# HA_HiPower.net
KiCad netlist of a schematic drawn in Altium Designer
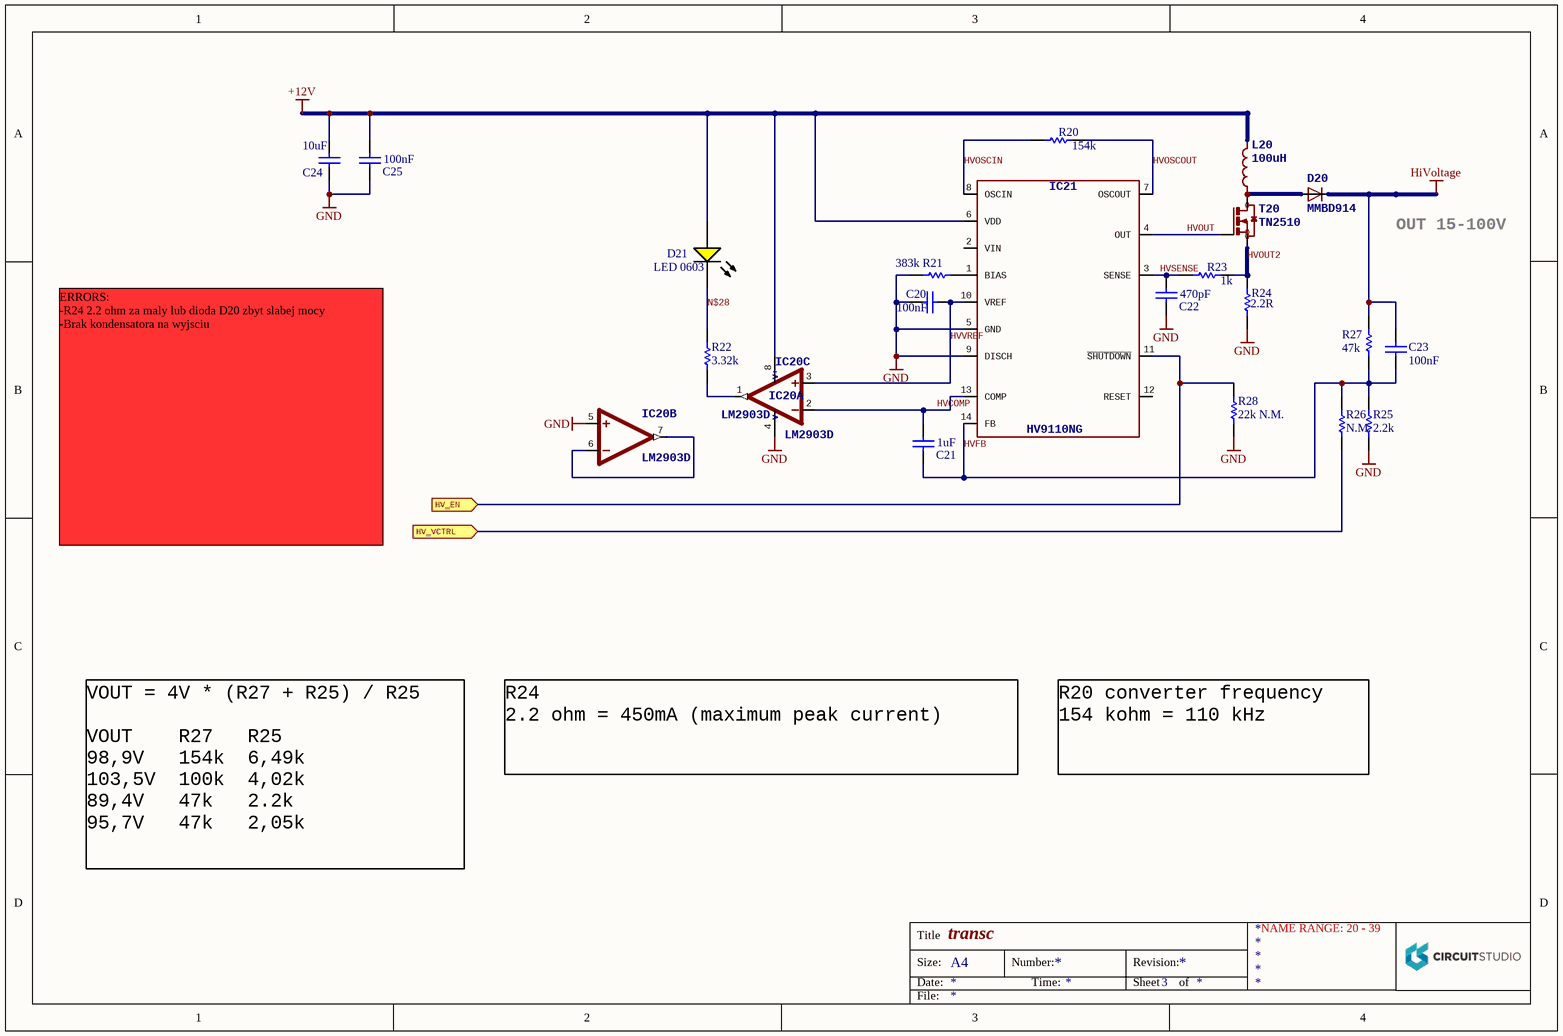
[diagram p0: HA_HiPower.SchDoc]

(export (version "E")
  (design (tool "Eeschema 10.0.6"))
  (components
    (comp (ref "C20")
      (value "100nF")
      (footprint "CAPC0805(2012)145_L")
      (fields (field (name "TOLERANCE") "Â±20%") (field (name "Comment") "100nF 100V"))
      (libsource (lib "Altium Content Vault") (part "CMP-1036-04431-1"))
    )
    (comp (ref "C21")
      (value "1uF")
      (footprint "CAPC0805(2012)145_L")
      (fields (field (name "TOLERANCE") "Â±20%") (field (name "Comment") "1uF 100V"))
      (libsource (lib "Altium Content Vault") (part "CMP-1036-04431-1"))
    )
    (comp (ref "C22")
      (value "470pF")
      (footprint "CAPC0805(2012)145_L")
      (fields (field (name "TOLERANCE") "Â±20%") (field (name "Comment") "470pF 100V"))
      (libsource (lib "Altium Content Vault") (part "CMP-1036-04431-1"))
    )
    (comp (ref "C23")
      (value "100nF")
      (footprint "CAPC0805(2012)145_L")
      (fields (field (name "TOLERANCE") "Â±20%") (field (name "Comment") "100nF 100V"))
      (libsource (lib "Altium Content Vault") (part "CMP-1036-04431-1"))
    )
    (comp (ref "C24")
      (value "10uF")
      (footprint "CAPC1206(3216)190_N")
      (description "CAP 1206 (3216 Metric) Thickness 1.9mm SMD")
      (fields (field (name "TOLERANCE") "Â±20%") (field (name "Comment") "10uF 35V"))
      (libsource (lib "Altium Content Vault") (part "CMP-1037-04990-1"))
    )
    (comp (ref "C25")
      (value "100nF")
      (footprint "CAPC0805(2012)145_L")
      (fields (field (name "TOLERANCE") "Â±20%") (field (name "Comment") "100nF 100V"))
      (libsource (lib "Altium Content Vault") (part "CMP-1036-04431-1"))
    )
    (comp (ref "D20")
      (value "MMBD914")
      (footprint "SOT23")
      (libsource (lib "_toan_elem") (part "DIODE-SOT23"))
    )
    (comp (ref "D21")
      (value "LED 0603")
      (footprint "LTST-C190KSKT_V")
      (fields (field (name "TOLERANCE") "1%"))
      (libsource (lib "Altium Content Vault") (part "CMP-1674-00009-1"))
    )
    (comp (ref "IC20")
      (value "LM2903D")
      (footprint "SO08")
      (description "COMPARATOR")
      (fields (field (name "V+") "V+") (field (name "V-") "V-"))
      (libsource (lib "uw") (part "LM2903D"))
    )
    (comp (ref "IC21")
      (value "HV9110NG")
      (footprint "SOIC14")
      (libsource (lib "microchip") (part "HV9110NG"))
    )
    (comp (ref "L20")
      (value "100uH")
      (footprint "LPS8045B")
      (fields (field (name "MPN") "LPS8045B-104"))
      (libsource (lib "_toan_elem") (part "LDE1205"))
    )
    (comp (ref "R20")
      (value "154k")
      (footprint "RESC0603(1608)_N")
      (description "1% 0603 SMD")
      (fields (field (name "TOLERANCE") "1 %"))
      (libsource (lib "Altium Content Vault") (part "CMP-1012-00122-1"))
    )
    (comp (ref "R21")
      (value "383k")
      (footprint "RESC0603(1608)_N")
      (description "1% 0603 SMD")
      (fields (field (name "TOLERANCE") "1 %"))
      (libsource (lib "Altium Content Vault") (part "CMP-1012-00122-1"))
    )
    (comp (ref "R22")
      (value "3.32k")
      (footprint "RESC0603(1608)_N")
      (description "1% 0603 SMD")
      (fields (field (name "TOLERANCE") "1 %"))
      (libsource (lib "Altium Content Vault") (part "CMP-1012-00122-1"))
    )
    (comp (ref "R23")
      (value "1k")
      (footprint "RESC0603(1608)_N")
      (description "1% 0603 SMD")
      (fields (field (name "TOLERANCE") "1 %"))
      (libsource (lib "Altium Content Vault") (part "CMP-1012-00122-1"))
    )
    (comp (ref "R24")
      (value "2.2R")
      (footprint "RESC2512(6432)_M")
      (description "2.2R 1W 5% 2512 SMD")
      (fields (field (name "TOLERANCE") "5 %") (field (name "POWER") "1 W"))
      (libsource (lib "Altium Content Vault") (part "CMP-1018-00050-1"))
    )
    (comp (ref "R25")
      (value "2.2k")
      (footprint "RESC0603(1608)_N")
      (description "1% 0603 SMD")
      (fields (field (name "TOLERANCE") "1 %"))
      (libsource (lib "Altium Content Vault") (part "CMP-1012-00122-1"))
    )
    (comp (ref "R26")
      (value "N.M.")
      (footprint "RESC0603(1608)_N")
      (description "1% 0603 SMD")
      (fields (field (name "TOLERANCE") "1 %"))
      (libsource (lib "Altium Content Vault") (part "CMP-1012-00122-1"))
    )
    (comp (ref "R27")
      (value "47k")
      (footprint "RESC0603(1608)_N")
      (description "1% 0603 SMD")
      (fields (field (name "TOLERANCE") "1 %"))
      (libsource (lib "Altium Content Vault") (part "CMP-1012-00122-1"))
    )
    (comp (ref "R28")
      (value "22k N.M.")
      (footprint "RESC0603(1608)_N")
      (description "1% 0603 SMD")
      (fields (field (name "TOLERANCE") "1 %"))
      (libsource (lib "Altium Content Vault") (part "CMP-1012-00122-1"))
    )
    (comp (ref "T20") (value "TN2510") (footprint "SOT89") (libsource (lib "uw") (part "MOSFET_NSOT89")))
  )
  (nets
    (net (code "1") (name "+12V") (class "Default")
      (node (ref "C24") (pin "2") (pinfunction "2_2") (pintype "passive"))
      (node (ref "C25") (pin "2") (pinfunction "2_2") (pintype "passive"))
      (node (ref "D21") (pin "1") (pinfunction "A_1") (pintype "passive"))
      (node (ref "IC20") (pin "8") (pinfunction "V+_8") (pintype "power_in"))
      (node (ref "IC21") (pin "6") (pinfunction "VDD_6") (pintype "power_in"))
      (node (ref "L20") (pin "2") (pinfunction "2_2") (pintype "passive"))
    )
    (net (code "2") (name "/HVCOMP") (class "Default")
      (node (ref "C21") (pin "2") (pinfunction "2_2") (pintype "passive"))
      (node (ref "IC20") (pin "2") (pinfunction "-IN_2") (pintype "passive"))
      (node (ref "IC21") (pin "13") (pinfunction "COMP_13") (pintype "passive"))
    )
    (net (code "3") (name "/HVFB") (class "Default")
      (node (ref "C21") (pin "1") (pinfunction "1_1") (pintype "passive"))
      (node (ref "C23") (pin "2") (pinfunction "2_2") (pintype "passive"))
      (node (ref "IC21") (pin "14") (pinfunction "FB_14") (pintype "passive"))
      (node (ref "R25") (pin "2") (pinfunction "2_2") (pintype "passive"))
      (node (ref "R26") (pin "2") (pinfunction "2_2") (pintype "passive"))
      (node (ref "R27") (pin "1") (pinfunction "1_1") (pintype "passive"))
    )
    (net (code "4") (name "/HVOSCIN") (class "Default")
      (node (ref "IC21") (pin "8") (pinfunction "OSCIN_8") (pintype "passive"))
      (node (ref "R20") (pin "1") (pinfunction "1_1") (pintype "passive"))
    )
    (net (code "5") (name "/HVOSCOUT") (class "Default")
      (node (ref "IC21") (pin "7") (pinfunction "OSCOUT_7") (pintype "passive"))
      (node (ref "R20") (pin "2") (pinfunction "2_2") (pintype "passive"))
    )
    (net (code "6") (name "/HVOUT") (class "Default")
      (node (ref "IC21") (pin "4") (pinfunction "OUT_4") (pintype "passive"))
      (node (ref "T20") (pin "1") (pinfunction "G_1") (pintype "passive"))
    )
    (net (code "7") (name "/HVOUT2") (class "Default")
      (node (ref "R23") (pin "2") (pinfunction "2_2") (pintype "passive"))
      (node (ref "R24") (pin "2") (pinfunction "2_2") (pintype "passive"))
      (node (ref "T20") (pin "3") (pinfunction "S_3") (pintype "passive"))
    )
    (net (code "8") (name "/HVSENSE") (class "Default")
      (node (ref "C22") (pin "2") (pinfunction "2_2") (pintype "passive"))
      (node (ref "IC21") (pin "3") (pinfunction "SENSE_3") (pintype "passive"))
      (node (ref "R23") (pin "1") (pinfunction "1_1") (pintype "passive"))
    )
    (net (code "9") (name "/HVVREF") (class "Default")
      (node (ref "C20") (pin "1") (pinfunction "1_1") (pintype "passive"))
      (node (ref "IC20") (pin "3") (pinfunction "+IN_3") (pintype "passive"))
      (node (ref "IC21") (pin "10") (pinfunction "VREF_10") (pintype "passive"))
    )
    (net (code "10") (name "/HV_EN") (class "Default")
      (node (ref "IC21") (pin "11") (pinfunction "~{SHUTDOWN}_11") (pintype "passive"))
      (node (ref "R28") (pin "2") (pinfunction "2_2") (pintype "passive"))
    )
    (net (code "11") (name "/HV_VCTRL") (class "Default")
      (node (ref "R26") (pin "1") (pinfunction "1_1") (pintype "passive"))
    )
    (net (code "12") (name "/N$28") (class "Default")
      (node (ref "D21") (pin "2") (pinfunction "K_2") (pintype "passive"))
      (node (ref "R22") (pin "1") (pinfunction "1_1") (pintype "passive"))
    )
    (net (code "13") (name "GND") (class "Default")
      (node (ref "C20") (pin "2") (pinfunction "2_2") (pintype "passive"))
      (node (ref "C22") (pin "1") (pinfunction "1_1") (pintype "passive"))
      (node (ref "C24") (pin "1") (pinfunction "1_1") (pintype "passive"))
      (node (ref "C25") (pin "1") (pinfunction "1_1") (pintype "passive"))
      (node (ref "IC20") (pin "4") (pinfunction "V-_4") (pintype "power_in"))
      (node (ref "IC20") (pin "5") (pinfunction "+IN_5") (pintype "passive"))
      (node (ref "IC21") (pin "5") (pinfunction "GND_5") (pintype "power_in"))
      (node (ref "IC21") (pin "9") (pinfunction "DISCH_9") (pintype "passive"))
      (node (ref "R21") (pin "1") (pinfunction "1_1") (pintype "passive"))
      (node (ref "R24") (pin "1") (pinfunction "1_1") (pintype "passive"))
      (node (ref "R25") (pin "1") (pinfunction "1_1") (pintype "passive"))
      (node (ref "R28") (pin "1") (pinfunction "1_1") (pintype "passive"))
    )
    (net (code "14") (name "HiVoltage") (class "Default")
      (node (ref "C23") (pin "1") (pinfunction "1_1") (pintype "passive"))
      (node (ref "D20") (pin "C") (pinfunction "C_C") (pintype "passive"))
      (node (ref "R27") (pin "2") (pinfunction "2_2") (pintype "passive"))
    )
    (net (code "15") (name "Net-(D20-A)") (class "Default")
      (node (ref "D20") (pin "B") (pinfunction "A_B") (pintype "passive"))
      (node (ref "L20") (pin "1") (pinfunction "1_1") (pintype "passive"))
      (node (ref "T20") (pin "2") (pinfunction "D_2") (pintype "passive"))
    )
    (net (code "16") (name "Net-(IC20A-OUT)") (class "Default")
      (node (ref "IC20") (pin "1") (pinfunction "OUT_1") (pintype "output"))
      (node (ref "R22") (pin "2") (pinfunction "2_2") (pintype "passive"))
    )
    (net (code "17") (name "Net-(IC20B--IN)") (class "Default")
      (node (ref "IC20") (pin "6") (pinfunction "-IN_6") (pintype "passive"))
      (node (ref "IC20") (pin "7") (pinfunction "OUT_7") (pintype "output"))
    )
    (net (code "18") (name "Net-(IC21-BIAS)") (class "Default")
      (node (ref "IC21") (pin "1") (pinfunction "BIAS_1") (pintype "passive"))
      (node (ref "R21") (pin "2") (pinfunction "2_2") (pintype "passive"))
    )
    (net (code "19") (name "unconnected-(IC21-RESET-Pad12)") (class "Default")
      (node (ref "IC21") (pin "12") (pinfunction "RESET_12") (pintype "passive"))
    )
    (net (code "20") (name "unconnected-(IC21-VIN-Pad2)") (class "Default")
      (node (ref "IC21") (pin "2") (pinfunction "VIN_2") (pintype "passive"))
    )
  )
)
